# SCH_Grove_Lepton_camera_2022-09-28.net
KiCad netlist of a schematic drawn in EasyEDA
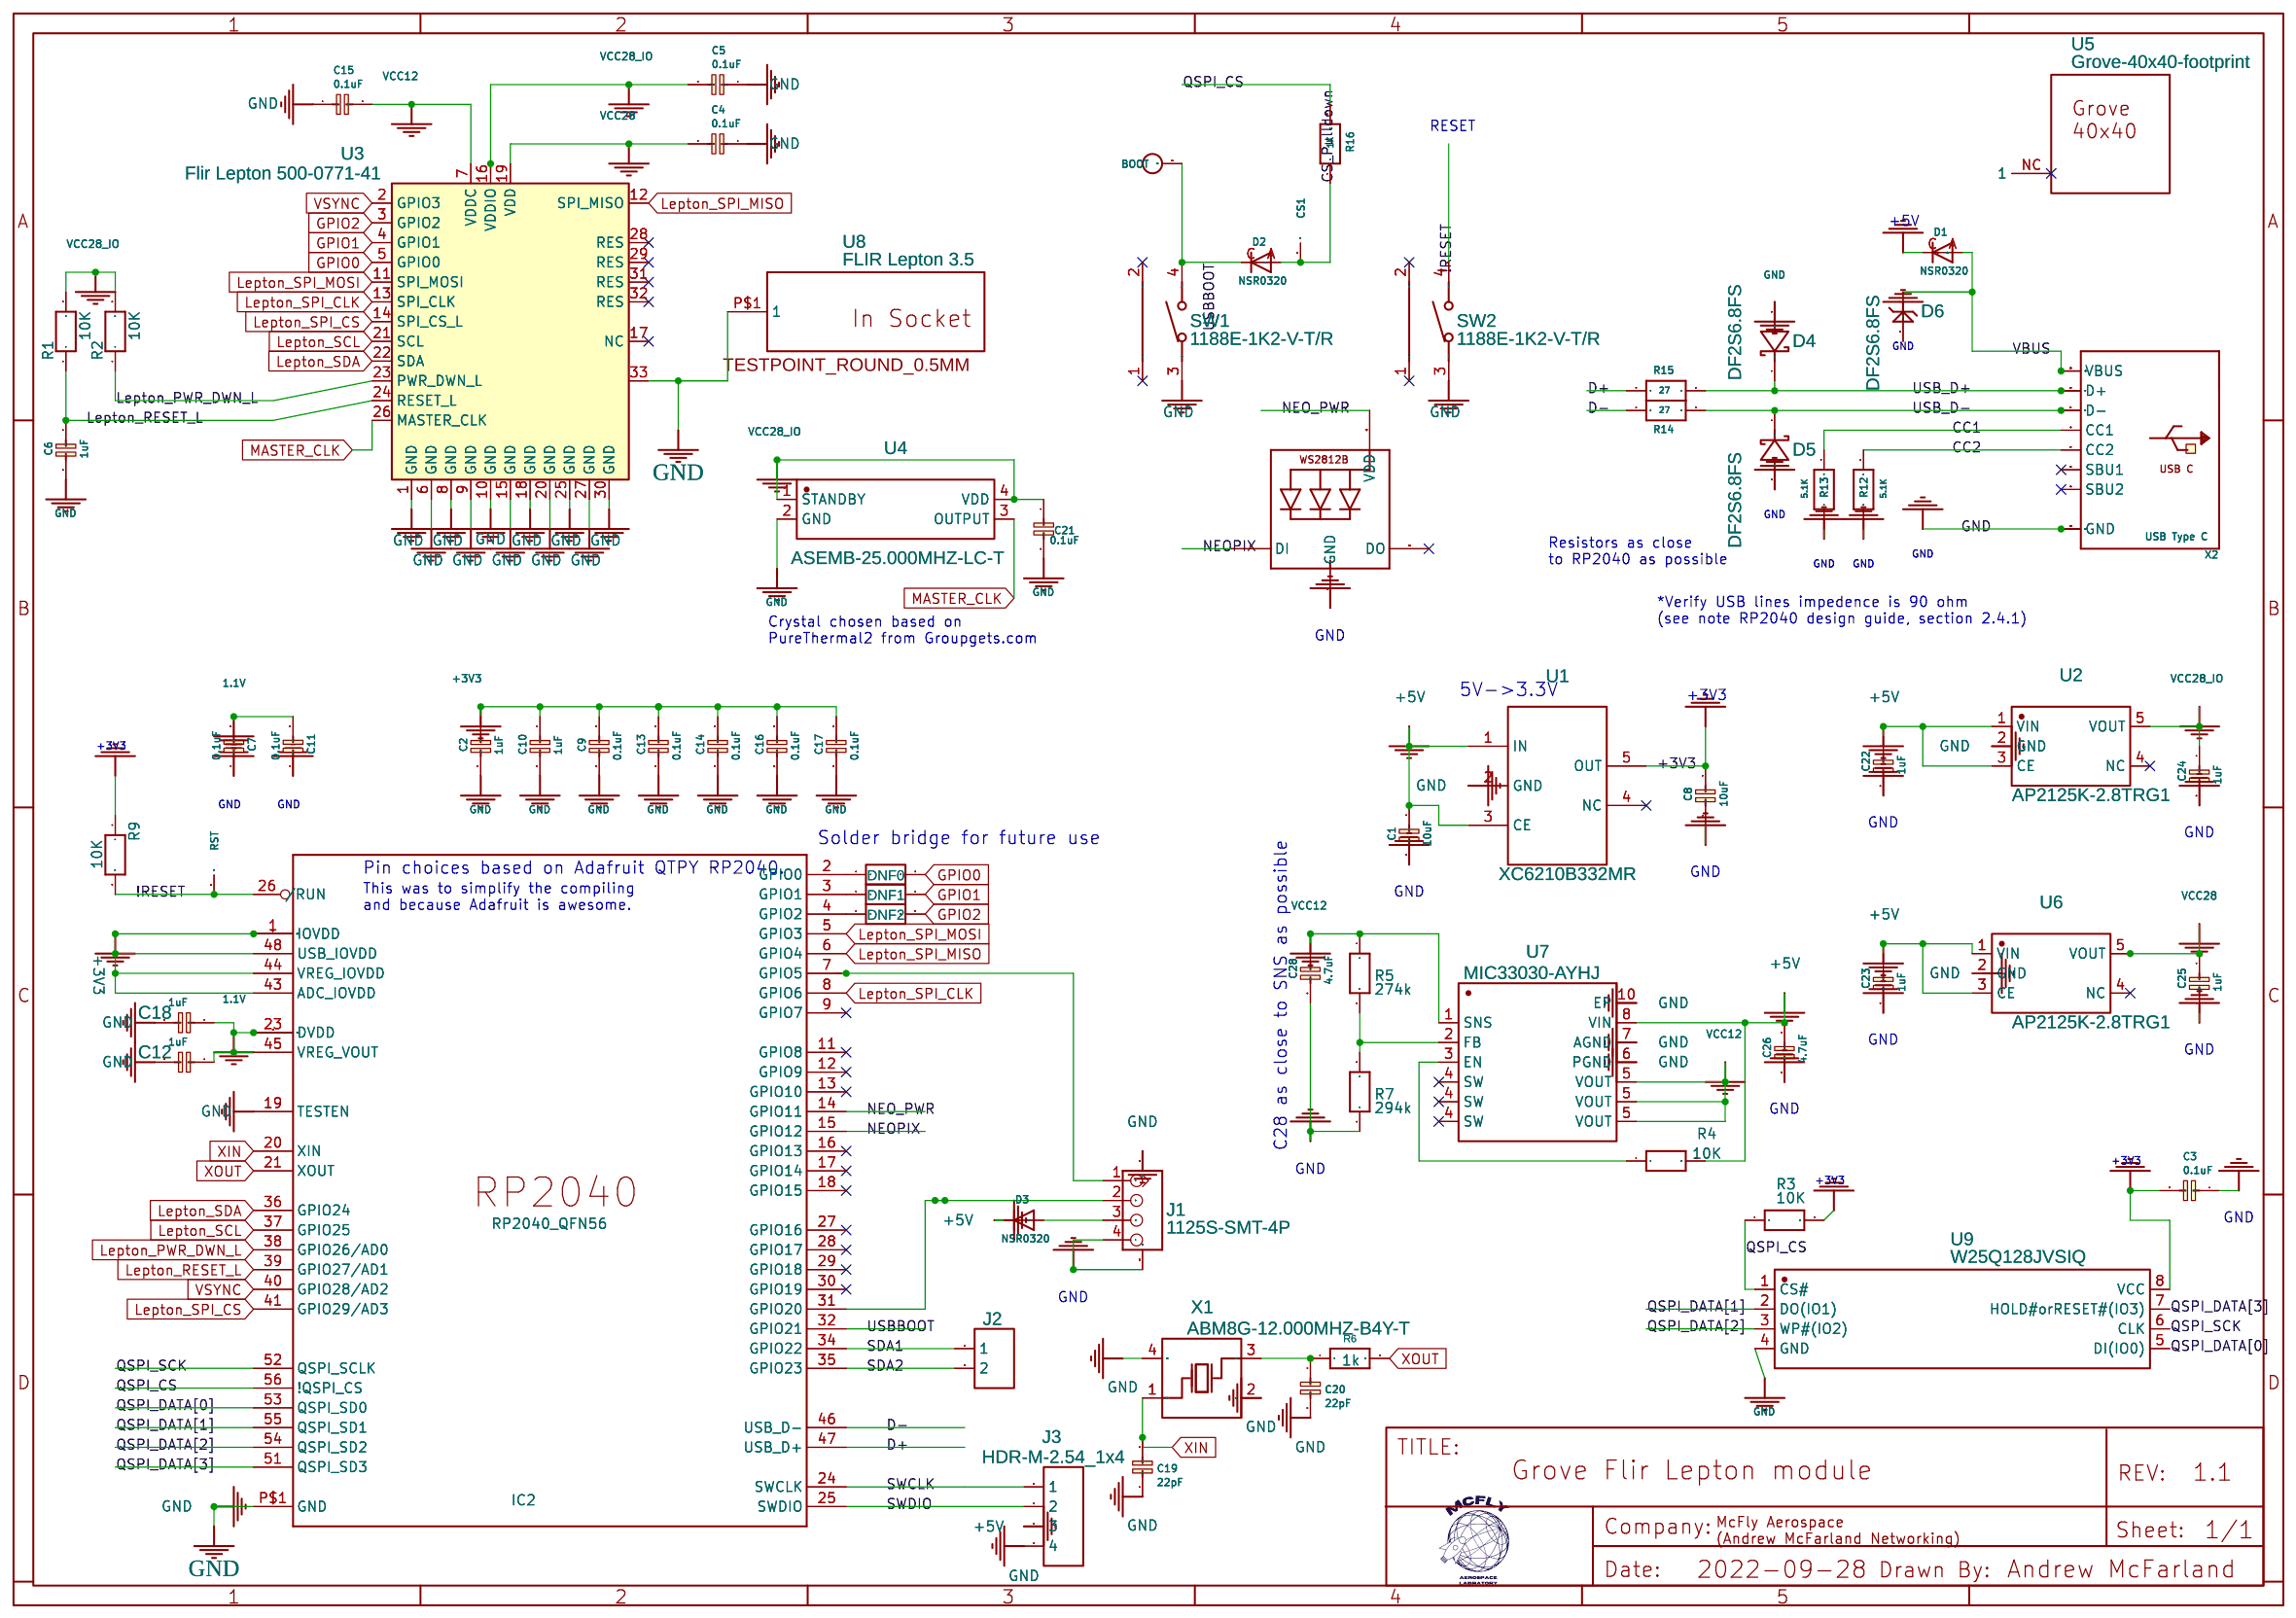
[diagram p0: schematic sheet]

(export (version "E")
  (design (tool "Eeschema 10.0.6"))
  (components
    (comp (ref "BOOT") (value "TESTPOINTROUND1.5MMNO") (libsource (lib "") (part "Unknown_595_-730")))
    (comp (ref "C1")
      (value "10uF")
      (fields
        (field (name "Manufacturer Part") "CC0805ZKY5V6BB106")
        (field (name "BOM_Supplier Part") "302010158")
      )
      (libsource (lib "") (part "Unknown_710_-385"))
    )
    (comp (ref "C2")
      (value "1uF")
      (fields
        (field (name "Manufacturer Part") "CC0603KRX7R8BB105")
        (field (name "BOM_Supplier Part") "302010139")
      )
      (libsource (lib "") (part "Unknown_240_-430"))
    )
    (comp (ref "C3")
      (value "0.1uF")
      (fields
        (field (name "Manufacturer Part") "CC0402KRX7R7BB104")
        (field (name "BOM_Supplier Part") "302010004")
      )
      (libsource (lib "") (part "Unknown_1100_-210"))
    )
    (comp (ref "C4") (value "0.1uF") (libsource (lib "") (part "Unknown_355_-740")))
    (comp (ref "C5") (value "0.1uF") (libsource (lib "") (part "Unknown_355_-770")))
    (comp (ref "C6") (value "1uF") (libsource (lib "") (part "Unknown_30_-580")))
    (comp (ref "C7") (value "0.1uF") (libsource (lib "") (part "Unknown_115_-440")))
    (comp (ref "C8") (value "10uF") (libsource (lib "") (part "Unknown_860_-405")))
    (comp (ref "C9") (value "0.1uF") (libsource (lib "") (part "Unknown_300_-430")))
    (comp (ref "C10") (value "1uF") (libsource (lib "") (part "Unknown_270_-430")))
    (comp (ref "C11") (value "0.1uF") (libsource (lib "") (part "Unknown_145_-440")))
    (comp (ref "C12") (value "1uF") (libsource (lib "") (part "Unknown_85_-275")))
    (comp (ref "C13") (value "0.1uF") (libsource (lib "") (part "Unknown_330_-430")))
    (comp (ref "C14") (value "0.1uF") (libsource (lib "") (part "Unknown_360_-430")))
    (comp (ref "C15") (value "0.1uF") (libsource (lib "") (part "Unknown_175_-760")))
    (comp (ref "C16") (value "0.1uF") (libsource (lib "") (part "Unknown_390_-430")))
    (comp (ref "C17") (value "0.1uF") (libsource (lib "") (part "Unknown_420_-430")))
    (comp (ref "C18") (value "1uF") (libsource (lib "") (part "Unknown_85_-295")))
    (comp (ref "C19") (value "22pF") (libsource (lib "") (part "Unknown_575_-75")))
    (comp (ref "C20")
      (value "22pF")
      (fields
        (field (name "Manufacturer Part") "CC0402JRNPO9BN220")
        (field (name "BOM_Supplier Part") "302010018")
      )
      (libsource (lib "") (part "Unknown_660_-105"))
    )
    (comp (ref "C21") (value "0.1uF") (libsource (lib "") (part "Unknown_525_-540")))
    (comp (ref "C22") (value "1uF") (libsource (lib "") (part "Unknown_950_-420")))
    (comp (ref "C23") (value "1uF") (libsource (lib "") (part "Unknown_950_-310")))
    (comp (ref "C24") (value "1uF") (libsource (lib "") (part "Unknown_1110_-415")))
    (comp (ref "C25") (value "1uF") (libsource (lib "") (part "Unknown_1110_-310")))
    (comp (ref "C26")
      (value "4.7uF")
      (fields
        (field (name "Manufacturer Part") "CC0805KKX5R8BB475")
        (field (name "BOM_Supplier Part") "302010146")
      )
      (libsource (lib "") (part "Unknown_900_-275"))
    )
    (comp (ref "C28")
      (value "4.7uF")
      (fields (field (name "BOM_Supplier Part") "302010146"))
      (libsource (lib "") (part "Unknown_660_-315"))
    )
    (comp (ref "CS1") (value "TESTPOINTROUND1.5MMNO") (libsource (lib "") (part "Unknown_655_-680")))
    (comp (ref "D1")
      (value "NSR0320")
      (fields
        (field (name "Manufacturer Part") "NSR0320MW2T1G")
        (field (name "BOM_Supplier Part") "NSR0320MW2T1GOSTR-ND")
      )
      (libsource (lib "") (part "Unknown_980_-685"))
    )
    (comp (ref "D2")
      (value "NSR0320")
      (fields
        (field (name "Manufacturer Part") "NSR0320MW2T1G")
        (field (name "BOM_Supplier Part") "NSR0320MW2T1GOSCT-ND")
      )
      (libsource (lib "") (part "Unknown_635_-680"))
    )
    (comp (ref "D3")
      (value "NSR0320")
      (fields
        (field (name "Manufacturer Part") "NSR0320MW2T1G")
        (field (name "BOM_Supplier Part") "NSR0320MW2T1GOSCT-ND")
      )
      (libsource (lib "") (part "Unknown_515_-195"))
    )
    (comp (ref "D4")
      (value "DF2S6.8FS")
      (fields
        (field (name "BOM_Manufacturer Part") "DF2S6.8FS,L3M")
        (field (name "BOM_Supplier Part") "304060009")
      )
      (libsource (lib "") (part "DF2S6.8FS,L3M"))
    )
    (comp (ref "D5")
      (value "DF2S6.8FS")
      (fields
        (field (name "BOM_Manufacturer Part") "DF2S6.8FS,L3M")
        (field (name "BOM_Supplier Part") "304060009")
      )
      (libsource (lib "") (part "DF2S6.8FS,L3M_1"))
    )
    (comp (ref "D6")
      (value "DF2S6.8FS")
      (fields (field (name "BOM_Supplier Part") "304060009"))
      (libsource (lib "") (part "D-ESD-2PDF2S6.8FS"))
    )
    (comp (ref "DNF0") (value "DNF") (libsource (lib "") (part "R_0603_EU")))
    (comp (ref "DNF1") (value "DNF") (libsource (lib "") (part "R_0603_EU")))
    (comp (ref "DNF2") (value "DNF") (libsource (lib "") (part "R_0603_EU")))
    (comp (ref "IC2")
      (value "RP2040_QFN56")
      (fields (field (name "Manufacturer Part") "RP2040") (field (name "BOM_Supplier Part") "310011401"))
      (libsource (lib "") (part "Unknown_275_-210"))
    )
    (comp (ref "J1")
      (value "1125S-SMT-4P")
      (fields (field (name "BOM_Supplier Part") "320110030"))
      (libsource (lib "") (part "1125S-SMT-4P"))
    )
    (comp (ref "J2") (value "HDR-F-2.54_1x2") (libsource (lib "") (part "HDR-F-2.54_1x2")))
    (comp (ref "J3") (value "HDR-M-2.54_1x4") (libsource (lib "") (part "HDR-M-2.54_1x4")))
    (comp (ref "LED1")
      (value "WS2812B_SK6805_1515")
      (fields (field (name "Manufacturer Part") "WS2812B-V5") (field (name "BOM_Supplier Part") "304091310"))
      (libsource (lib "") (part "Unknown_670_-545"))
    )
    (comp (ref "R1")
      (value "10K")
      (fields
        (field (name "Manufacturer Part") "RC0402JR-0710KL")
        (field (name "BOM_Supplier Part") "301010004")
      )
      (libsource (lib "") (part "Unknown_30_-645"))
    )
    (comp (ref "R2")
      (value "10K")
      (fields
        (field (name "Manufacturer Part") "RC0402JR-0710KL")
        (field (name "BOM_Supplier Part") "301010004")
      )
      (libsource (lib "") (part "Unknown_55_-645"))
    )
    (comp (ref "R3")
      (value "10K")
      (fields
        (field (name "Manufacturer Part") "RC0402JR-0710KL")
        (field (name "BOM_Supplier Part") "301010004")
      )
      (libsource (lib "") (part "Unknown_900_-195"))
    )
    (comp (ref "R4")
      (value "10K")
      (fields
        (field (name "Manufacturer Part") "RC0402JR-0710KL")
        (field (name "BOM_Supplier Part") "301010004")
      )
      (libsource (lib "") (part "Unknown_840_-225"))
    )
    (comp (ref "R5")
      (value "274k")
      (fields (field (name "BOM_Supplier Part") "RC0402FR-07274KL"))
      (libsource (lib "") (part "Unknown_685_-320"))
    )
    (comp (ref "R6")
      (value "1k")
      (fields
        (field (name "Manufacturer Part") "RC0402FR-071KL")
        (field (name "BOM_Supplier Part") "301010044")
      )
      (libsource (lib "") (part "Unknown_680_-125"))
    )
    (comp (ref "R7")
      (value "294k")
      (fields (field (name "BOM_Supplier Part") "RC0402FR-07294KL"))
      (libsource (lib "") (part "Unknown_685_-260"))
    )
    (comp (ref "R9")
      (value "10K")
      (fields
        (field (name "Manufacturer Part") "RC0402JR-0710KL")
        (field (name "BOM_Supplier Part") "301010004")
      )
      (libsource (lib "") (part "Unknown_55_-380"))
    )
    (comp (ref "R12")
      (value "5.1K")
      (fields
        (field (name "Manufacturer Part") "RC0402FR-075K1L")
        (field (name "BOM_Supplier Part") "301010495")
      )
      (libsource (lib "") (part "Unknown_940_-565"))
    )
    (comp (ref "R13")
      (value "5.1K")
      (fields
        (field (name "Manufacturer Part") "RC0402FR-075K1L")
        (field (name "BOM_Supplier Part") "301010495")
      )
      (libsource (lib "") (part "Unknown_920_-565"))
    )
    (comp (ref "R14")
      (value "27")
      (fields
        (field (name "Manufacturer Part") "RC0603FR-0727RL")
        (field (name "BOM_Supplier Part") "301011528")
      )
      (libsource (lib "") (part "Unknown_840_-605"))
    )
    (comp (ref "R15")
      (value "27")
      (fields
        (field (name "Manufacturer Part") "RC0603FR-0727RL")
        (field (name "BOM_Supplier Part") "301011528")
      )
      (libsource (lib "") (part "Unknown_840_-615"))
    )
    (comp (ref "R16")
      (value "1K")
      (fields
        (field (name "Manufacturer Part") "RC0402FR-071KL")
        (field (name "BOM_Supplier Part") "301010044")
      )
      (libsource (lib "") (part "Unknown_670_-740"))
    )
    (comp (ref "RST") (value "TESTPOINTROUND1.5MMNO") (libsource (lib "") (part "Unknown_105_-360")))
    (comp (ref "SW1")
      (value "1188E-1K2-V-T/R")
      (fields (field (name "BOM_Supplier Part") "311020023"))
      (libsource (lib "") (part "1188E-1K2-V-T/R"))
    )
    (comp (ref "SW2")
      (value "1188E-1K2-V-T/R")
      (fields (field (name "BOM_Supplier Part") "311020023"))
      (libsource (lib "") (part "1188E-1K2-V-T/R"))
    )
    (comp (ref "U1")
      (value "XC6210B332MR")
      (fields (field (name "BOM_Supplier Part") "893-1075-1-ND"))
      (libsource (lib "") (part "XC6210B332MR"))
    )
    (comp (ref "U2")
      (value "AP2125K-2.8TRG1")
      (fields (field (name "BOM_Supplier Part") "AP2125K-2.8TRG1DICT-ND"))
      (libsource (lib "") (part "AP2125K-2.8TRG1"))
    )
    (comp (ref "U3")
      (value "Flir Lepton 500-0771-41")
      (fields
        (field (name "BOM_Manufacturer Part") "1050281001")
        (field (name "BOM_Supplier Part") "WM6827CT-ND")
      )
      (libsource (lib "") (part "500-0643-00"))
    )
    (comp (ref "U4")
      (value "ASEMB-25.000MHZ-LC-T")
      (fields (field (name "BOM_Manufacturer Part") "535-11750-2-ND - 卷带（TR） 535-11750-1-ND"))
      (libsource (lib "") (part "ASEMB-25.000MHZ-LY-T"))
    )
    (comp (ref "U5") (value "Grove-40x40-footprint") (libsource (lib "") (part "Grove-40x40-footprint")))
    (comp (ref "U6")
      (value "AP2125K-2.8TRG1")
      (fields (field (name "BOM_Supplier Part") "AP2125K-2.8TRG1DICT-ND"))
      (libsource (lib "") (part "AP2125K-2.8TRG1"))
    )
    (comp (ref "U7")
      (value "MIC33030-AYHJ")
      (fields
        (field (name "BOM_Manufacturer Part") "MIC33030-AYHJ-TR")
        (field (name "BOM_Supplier Part") "998-MIC33030-AYHJTR")
      )
      (libsource (lib "") (part "MIC33030-AYHJ-TR"))
    )
    (comp (ref "U8")
      (value "FLIR Lepton 3.5")
      (fields
        (field (name "BOM_Manufacturer Part") "500-0771-01-ND")
        (field (name "BOM_Supplier Part") "500-0771-01")
      )
      (libsource (lib "") (part "lepton"))
    )
    (comp (ref "U9") (value "W25Q128JVSIQ") (libsource (lib "") (part "W25Q128JVSIQ")))
    (comp (ref "X1") (value "ABM8G-12.000MHZ-B4Y-T") (libsource (lib "") (part "ABM8G-12.000MHZ-B4Y-T")))
    (comp (ref "X2") (value "USB Type C") (libsource (lib "") (part "Unknown_1080_-585")))
  )
  (nets
    (net (code "1") (name "+3V3") (class "Default")
      (node (ref "C10") (pin "1") (pinfunction "1_1") (pintype "bidirectional"))
      (node (ref "C13") (pin "1") (pinfunction "1_1") (pintype "bidirectional"))
      (node (ref "C14") (pin "1") (pinfunction "1_1") (pintype "bidirectional"))
      (node (ref "C16") (pin "1") (pinfunction "1_1") (pintype "bidirectional"))
      (node (ref "C17") (pin "1") (pinfunction "1_1") (pintype "bidirectional"))
      (node (ref "C2") (pin "1") (pinfunction "1_1") (pintype "bidirectional"))
      (node (ref "C3") (pin "2") (pinfunction "2_2") (pintype "bidirectional"))
      (node (ref "C8") (pin "1") (pinfunction "1_1") (pintype "bidirectional"))
      (node (ref "C9") (pin "1") (pinfunction "1_1") (pintype "bidirectional"))
      (node (ref "IC2") (pin "1") (pinfunction "IOVDD_1") (pintype "bidirectional"))
      (node (ref "IC2") (pin "10") (pinfunction "IOVDD_10") (pintype "bidirectional"))
      (node (ref "IC2") (pin "22") (pinfunction "IOVDD_22") (pintype "bidirectional"))
      (node (ref "IC2") (pin "33") (pinfunction "IOVDD_33") (pintype "bidirectional"))
      (node (ref "IC2") (pin "42") (pinfunction "IOVDD_42") (pintype "bidirectional"))
      (node (ref "IC2") (pin "43") (pinfunction "ADC_IOVDD_43") (pintype "bidirectional"))
      (node (ref "IC2") (pin "44") (pinfunction "VREG_IOVDD_44") (pintype "bidirectional"))
      (node (ref "IC2") (pin "48") (pinfunction "USB_IOVDD_48") (pintype "bidirectional"))
      (node (ref "IC2") (pin "49") (pinfunction "IOVDD_49") (pintype "bidirectional"))
      (node (ref "R3") (pin "2") (pinfunction "2_2") (pintype "bidirectional"))
      (node (ref "R9") (pin "1") (pinfunction "1_1") (pintype "bidirectional"))
      (node (ref "U1") (pin "5") (pinfunction "OUT_5") (pintype "unspecified"))
      (node (ref "U9") (pin "8") (pinfunction "VCC_8") (pintype "unspecified"))
    )
    (net (code "2") (name "+5V") (class "Default")
      (node (ref "C1") (pin "1") (pinfunction "1_1") (pintype "bidirectional"))
      (node (ref "C22") (pin "1") (pinfunction "1_1") (pintype "bidirectional"))
      (node (ref "C23") (pin "1") (pinfunction "1_1") (pintype "bidirectional"))
      (node (ref "C26") (pin "1") (pinfunction "1_1") (pintype "bidirectional"))
      (node (ref "D1") (pin "C") (pinfunction "Cathode_C") (pintype "bidirectional"))
      (node (ref "D3") (pin "C") (pinfunction "C_C") (pintype "bidirectional"))
      (node (ref "J3") (pin "3") (pinfunction "3_3") (pintype "unspecified"))
      (node (ref "R4") (pin "2") (pinfunction "2_2") (pintype "bidirectional"))
      (node (ref "U1") (pin "1") (pinfunction "IN_1") (pintype "unspecified"))
      (node (ref "U1") (pin "3") (pinfunction "CE_3") (pintype "unspecified"))
      (node (ref "U2") (pin "1") (pinfunction "VIN_1") (pintype "unspecified"))
      (node (ref "U2") (pin "3") (pinfunction "CE_3") (pintype "unspecified"))
      (node (ref "U6") (pin "1") (pinfunction "VIN_1") (pintype "unspecified"))
      (node (ref "U6") (pin "3") (pinfunction "CE_3") (pintype "unspecified"))
      (node (ref "U7") (pin "8") (pinfunction "VIN_8") (pintype "unspecified"))
    )
    (net (code "3") (name "/!RESET") (class "Default")
      (node (ref "IC2") (pin "26") (pinfunction "/RUN_26") (pintype "bidirectional"))
      (node (ref "R9") (pin "2") (pinfunction "2_2") (pintype "bidirectional"))
      (node (ref "RST") (pin "P$1") (pinfunction "P$1_P$1") (pintype "bidirectional"))
      (node (ref "SW2") (pin "4") (pinfunction "4_4") (pintype "unspecified"))
    )
    (net (code "4") (name "/CC1") (class "Default")
      (node (ref "R13") (pin "2") (pinfunction "2_2") (pintype "bidirectional"))
      (node (ref "X2") (pin "A5") (pinfunction "CC1_A5") (pintype "bidirectional"))
    )
    (net (code "5") (name "/CC2") (class "Default")
      (node (ref "R12") (pin "2") (pinfunction "2_2") (pintype "bidirectional"))
      (node (ref "X2") (pin "B5") (pinfunction "CC2_B5") (pintype "bidirectional"))
    )
    (net (code "6") (name "/CS_Pulldown") (class "Default")
      (node (ref "CS1") (pin "P$1") (pinfunction "P$1_P$1") (pintype "bidirectional"))
      (node (ref "D2") (pin "A") (pinfunction "A_A") (pintype "bidirectional"))
      (node (ref "R16") (pin "2") (pinfunction "2_2") (pintype "bidirectional"))
    )
    (net (code "7") (name "/D+") (class "Default")
      (node (ref "IC2") (pin "47") (pinfunction "USB_D+_47") (pintype "bidirectional"))
      (node (ref "R15") (pin "2") (pinfunction "2_2") (pintype "bidirectional"))
    )
    (net (code "8") (name "/D-") (class "Default")
      (node (ref "IC2") (pin "46") (pinfunction "USB_D-_46") (pintype "bidirectional"))
      (node (ref "R14") (pin "2") (pinfunction "2_2") (pintype "bidirectional"))
    )
    (net (code "9") (name "/NEOPIX") (class "Default")
      (node (ref "IC2") (pin "15") (pinfunction "GPIO12_15") (pintype "bidirectional"))
      (node (ref "LED1") (pin "4-DIN") (pinfunction "DI_4-DIN") (pintype "bidirectional"))
    )
    (net (code "10") (name "/NEO_PWR") (class "Default")
      (node (ref "IC2") (pin "14") (pinfunction "GPIO11_14") (pintype "bidirectional"))
      (node (ref "LED1") (pin "1-VDD") (pinfunction "VDD_1-VDD") (pintype "bidirectional"))
    )
    (net (code "11") (name "/QSPI_CS") (class "Default")
      (node (ref "IC2") (pin "56") (pinfunction "!QSPI_CS_56") (pintype "bidirectional"))
      (node (ref "R16") (pin "1") (pinfunction "1_1") (pintype "bidirectional"))
      (node (ref "R3") (pin "1") (pinfunction "1_1") (pintype "bidirectional"))
      (node (ref "U9") (pin "1") (pinfunction "CS#_1") (pintype "unspecified"))
    )
    (net (code "12") (name "/QSPI_DATA[0]") (class "Default")
      (node (ref "IC2") (pin "53") (pinfunction "QSPI_SD0_53") (pintype "bidirectional"))
      (node (ref "U9") (pin "5") (pinfunction "DI(IO0)_5") (pintype "unspecified"))
    )
    (net (code "13") (name "/QSPI_DATA[1]") (class "Default")
      (node (ref "IC2") (pin "55") (pinfunction "QSPI_SD1_55") (pintype "bidirectional"))
      (node (ref "U9") (pin "2") (pinfunction "DO(IO1)_2") (pintype "unspecified"))
    )
    (net (code "14") (name "/QSPI_DATA[2]") (class "Default")
      (node (ref "IC2") (pin "54") (pinfunction "QSPI_SD2_54") (pintype "bidirectional"))
      (node (ref "U9") (pin "3") (pinfunction "WP#(IO2)_3") (pintype "unspecified"))
    )
    (net (code "15") (name "/QSPI_DATA[3]") (class "Default")
      (node (ref "IC2") (pin "51") (pinfunction "QSPI_SD3_51") (pintype "bidirectional"))
      (node (ref "U9") (pin "7") (pinfunction "HOLD#orRESET#(IO3)_7") (pintype "unspecified"))
    )
    (net (code "16") (name "/QSPI_SCK") (class "Default")
      (node (ref "IC2") (pin "52") (pinfunction "QSPI_SCLK_52") (pintype "bidirectional"))
      (node (ref "U9") (pin "6") (pinfunction "CLK_6") (pintype "unspecified"))
    )
    (net (code "17") (name "/SDA1") (class "Default")
      (node (ref "IC2") (pin "34") (pinfunction "GPIO22_34") (pintype "bidirectional"))
      (node (ref "J2") (pin "1") (pinfunction "1_1") (pintype "input"))
    )
    (net (code "18") (name "/SDA2") (class "Default")
      (node (ref "IC2") (pin "35") (pinfunction "GPIO23_35") (pintype "bidirectional"))
      (node (ref "J2") (pin "2") (pinfunction "2_2") (pintype "input"))
    )
    (net (code "19") (name "/SWCLK") (class "Default")
      (node (ref "IC2") (pin "24") (pinfunction "SWCLK_24") (pintype "bidirectional"))
      (node (ref "J3") (pin "1") (pinfunction "1_1") (pintype "unspecified"))
    )
    (net (code "20") (name "/SWDIO") (class "Default")
      (node (ref "IC2") (pin "25") (pinfunction "SWDIO_25") (pintype "bidirectional"))
      (node (ref "J3") (pin "2") (pinfunction "2_2") (pintype "unspecified"))
    )
    (net (code "21") (name "/USBBOOT") (class "Default")
      (node (ref "BOOT") (pin "P$1") (pinfunction "P$1_P$1") (pintype "bidirectional"))
      (node (ref "D2") (pin "C") (pinfunction "C_C") (pintype "bidirectional"))
      (node (ref "IC2") (pin "32") (pinfunction "GPIO21_32") (pintype "bidirectional"))
      (node (ref "SW1") (pin "4") (pinfunction "4_4") (pintype "unspecified"))
    )
    (net (code "22") (name "/USB_D+") (class "Default")
      (node (ref "D4") (pin "1") (pinfunction "1_1") (pintype "unspecified"))
      (node (ref "R15") (pin "1") (pinfunction "1_1") (pintype "bidirectional"))
      (node (ref "X2") (pin "A6") (pinfunction "D+_A6") (pintype "bidirectional"))
      (node (ref "X2") (pin "B6") (pinfunction "D+_B6") (pintype "bidirectional"))
    )
    (net (code "23") (name "/USB_D-") (class "Default")
      (node (ref "D5") (pin "1") (pinfunction "1_1") (pintype "unspecified"))
      (node (ref "R14") (pin "1") (pinfunction "1_1") (pintype "bidirectional"))
      (node (ref "X2") (pin "A7") (pinfunction "D-_A7") (pintype "bidirectional"))
      (node (ref "X2") (pin "B7") (pinfunction "D-_B7") (pintype "bidirectional"))
    )
    (net (code "24") (name "/VBUS") (class "Default")
      (node (ref "D1") (pin "A") (pinfunction "Anode_A") (pintype "bidirectional"))
      (node (ref "D6") (pin "1") (pinfunction "2_1") (pintype "unspecified"))
      (node (ref "X2") (pin "A4B9") (pinfunction "VBUS_A4B9") (pintype "bidirectional"))
      (node (ref "X2") (pin "B4A9") (pinfunction "VBUS_B4A9") (pintype "bidirectional"))
    )
    (net (code "25") (name "1.1V") (class "Default")
      (node (ref "C11") (pin "2") (pinfunction "2_2") (pintype "bidirectional"))
      (node (ref "C12") (pin "1") (pinfunction "1_1") (pintype "bidirectional"))
      (node (ref "C18") (pin "1") (pinfunction "1_1") (pintype "bidirectional"))
      (node (ref "C7") (pin "2") (pinfunction "2_2") (pintype "bidirectional"))
      (node (ref "IC2") (pin "23") (pinfunction "DVDD_23") (pintype "bidirectional"))
      (node (ref "IC2") (pin "45") (pinfunction "VREG_VOUT_45") (pintype "bidirectional"))
      (node (ref "IC2") (pin "50") (pinfunction "DVDD_50") (pintype "bidirectional"))
    )
    (net (code "26") (name "GND") (class "Default")
      (node (ref "C1") (pin "2") (pinfunction "2_2") (pintype "bidirectional"))
      (node (ref "C10") (pin "2") (pinfunction "2_2") (pintype "bidirectional"))
      (node (ref "C11") (pin "1") (pinfunction "1_1") (pintype "bidirectional"))
      (node (ref "C12") (pin "2") (pinfunction "2_2") (pintype "bidirectional"))
      (node (ref "C13") (pin "2") (pinfunction "2_2") (pintype "bidirectional"))
      (node (ref "C14") (pin "2") (pinfunction "2_2") (pintype "bidirectional"))
      (node (ref "C15") (pin "1") (pinfunction "1_1") (pintype "bidirectional"))
      (node (ref "C16") (pin "2") (pinfunction "2_2") (pintype "bidirectional"))
      (node (ref "C17") (pin "2") (pinfunction "2_2") (pintype "bidirectional"))
      (node (ref "C18") (pin "2") (pinfunction "2_2") (pintype "bidirectional"))
      (node (ref "C19") (pin "1") (pinfunction "1_1") (pintype "bidirectional"))
      (node (ref "C2") (pin "2") (pinfunction "2_2") (pintype "bidirectional"))
      (node (ref "C20") (pin "2") (pinfunction "2_2") (pintype "bidirectional"))
      (node (ref "C21") (pin "2") (pinfunction "2_2") (pintype "bidirectional"))
      (node (ref "C22") (pin "2") (pinfunction "2_2") (pintype "bidirectional"))
      (node (ref "C23") (pin "2") (pinfunction "2_2") (pintype "bidirectional"))
      (node (ref "C24") (pin "2") (pinfunction "2_2") (pintype "bidirectional"))
      (node (ref "C25") (pin "2") (pinfunction "2_2") (pintype "bidirectional"))
      (node (ref "C26") (pin "2") (pinfunction "2_2") (pintype "bidirectional"))
      (node (ref "C28") (pin "2") (pinfunction "2_2") (pintype "bidirectional"))
      (node (ref "C3") (pin "1") (pinfunction "1_1") (pintype "bidirectional"))
      (node (ref "C4") (pin "1") (pinfunction "1_1") (pintype "bidirectional"))
      (node (ref "C5") (pin "1") (pinfunction "1_1") (pintype "bidirectional"))
      (node (ref "C6") (pin "2") (pinfunction "2_2") (pintype "bidirectional"))
      (node (ref "C7") (pin "1") (pinfunction "1_1") (pintype "bidirectional"))
      (node (ref "C8") (pin "2") (pinfunction "2_2") (pintype "bidirectional"))
      (node (ref "C9") (pin "2") (pinfunction "2_2") (pintype "bidirectional"))
      (node (ref "D4") (pin "2") (pinfunction "2_2") (pintype "unspecified"))
      (node (ref "D5") (pin "2") (pinfunction "2_2") (pintype "unspecified"))
      (node (ref "D6") (pin "2") (pinfunction "1_2") (pintype "unspecified"))
      (node (ref "IC2") (pin "19") (pinfunction "TESTEN_19") (pintype "bidirectional"))
      (node (ref "IC2") (pin "P$1") (pinfunction "GND_P$1") (pintype "bidirectional"))
      (node (ref "J1") (pin "4") (pinfunction "4_4") (pintype "unspecified"))
      (node (ref "J1") (pin "SS1") (pinfunction "SS1_SS1") (pintype "unspecified"))
      (node (ref "J1") (pin "SS2") (pinfunction "SS2_SS2") (pintype "unspecified"))
      (node (ref "J3") (pin "4") (pinfunction "4_4") (pintype "unspecified"))
      (node (ref "LED1") (pin "3-GND") (pinfunction "GND_3-GND") (pintype "bidirectional"))
      (node (ref "R12") (pin "1") (pinfunction "1_1") (pintype "bidirectional"))
      (node (ref "R13") (pin "1") (pinfunction "1_1") (pintype "bidirectional"))
      (node (ref "R7") (pin "2") (pinfunction "2_2") (pintype "bidirectional"))
      (node (ref "SW1") (pin "3") (pinfunction "3_3") (pintype "unspecified"))
      (node (ref "SW2") (pin "3") (pinfunction "3_3") (pintype "unspecified"))
      (node (ref "U1") (pin "2") (pinfunction "GND_2") (pintype "unspecified"))
      (node (ref "U2") (pin "2") (pinfunction "GND_2") (pintype "unspecified"))
      (node (ref "U3") (pin "1") (pinfunction "GND_1") (pintype "bidirectional"))
      (node (ref "U3") (pin "10") (pinfunction "GND_10") (pintype "bidirectional"))
      (node (ref "U3") (pin "15") (pinfunction "GND_15") (pintype "bidirectional"))
      (node (ref "U3") (pin "18") (pinfunction "GND_18") (pintype "bidirectional"))
      (node (ref "U3") (pin "20") (pinfunction "GND_20") (pintype "bidirectional"))
      (node (ref "U3") (pin "25") (pinfunction "GND_25") (pintype "bidirectional"))
      (node (ref "U3") (pin "27") (pinfunction "GND_27") (pintype "bidirectional"))
      (node (ref "U3") (pin "30") (pinfunction "GND_30") (pintype "bidirectional"))
      (node (ref "U3") (pin "33") (pintype "unspecified"))
      (node (ref "U3") (pin "6") (pinfunction "GND_6") (pintype "bidirectional"))
      (node (ref "U3") (pin "8") (pinfunction "GND_8") (pintype "bidirectional"))
      (node (ref "U3") (pin "9") (pinfunction "GND_9") (pintype "bidirectional"))
      (node (ref "U4") (pin "2") (pinfunction "GND_2") (pintype "unspecified"))
      (node (ref "U6") (pin "2") (pinfunction "GND_2") (pintype "unspecified"))
      (node (ref "U7") (pin "10") (pinfunction "EP_10") (pintype "unspecified"))
      (node (ref "U7") (pin "6") (pinfunction "PGND_6") (pintype "unspecified"))
      (node (ref "U7") (pin "7") (pinfunction "AGND_7") (pintype "unspecified"))
      (node (ref "U8") (pin "P$1") (pinfunction "1_P$1") (pintype "unspecified"))
      (node (ref "U9") (pin "4") (pinfunction "GND_4") (pintype "unspecified"))
      (node (ref "X1") (pin "2") (pinfunction "GND_2") (pintype "unspecified"))
      (node (ref "X1") (pin "4") (pinfunction "GND_4") (pintype "unspecified"))
      (node (ref "X2") (pin "A1B12") (pinfunction "GND_A1B12") (pintype "bidirectional"))
      (node (ref "X2") (pin "B1A12") (pinfunction "GND_B1A12") (pintype "bidirectional"))
    )
    (net (code "27") (name "GPIO0") (class "Default")
      (node (ref "DNF0") (pin "2") (pinfunction "2_2") (pintype "unspecified"))
      (node (ref "U3") (pin "5") (pinfunction "GPIO0_5") (pintype "bidirectional"))
    )
    (net (code "28") (name "GPIO1") (class "Default")
      (node (ref "DNF1") (pin "2") (pinfunction "2_2") (pintype "unspecified"))
      (node (ref "U3") (pin "4") (pinfunction "GPIO1_4") (pintype "bidirectional"))
    )
    (net (code "29") (name "GPIO2") (class "Default")
      (node (ref "DNF2") (pin "2") (pinfunction "2_2") (pintype "unspecified"))
      (node (ref "U3") (pin "3") (pinfunction "GPIO2_3") (pintype "bidirectional"))
    )
    (net (code "30") (name "Lepton_PWR_DWN_L") (class "Default")
      (node (ref "IC2") (pin "38") (pinfunction "GPIO26/AD0_38") (pintype "bidirectional"))
      (node (ref "R2") (pin "1") (pinfunction "1_1") (pintype "bidirectional"))
      (node (ref "U3") (pin "23") (pinfunction "PWR_DWN_L_23") (pintype "input"))
    )
    (net (code "31") (name "Lepton_RESET_L") (class "Default")
      (node (ref "C6") (pin "1") (pinfunction "1_1") (pintype "bidirectional"))
      (node (ref "IC2") (pin "39") (pinfunction "GPIO27/AD1_39") (pintype "bidirectional"))
      (node (ref "R1") (pin "1") (pinfunction "1_1") (pintype "bidirectional"))
      (node (ref "U3") (pin "24") (pinfunction "RESET_L_24") (pintype "input"))
    )
    (net (code "32") (name "Lepton_SCL") (class "Default")
      (node (ref "IC2") (pin "37") (pinfunction "GPIO25_37") (pintype "bidirectional"))
      (node (ref "U3") (pin "21") (pinfunction "SCL_21") (pintype "input"))
    )
    (net (code "33") (name "Lepton_SDA") (class "Default")
      (node (ref "IC2") (pin "36") (pinfunction "GPIO24_36") (pintype "bidirectional"))
      (node (ref "U3") (pin "22") (pinfunction "SDA_22") (pintype "bidirectional"))
    )
    (net (code "34") (name "Lepton_SPI_CLK") (class "Default")
      (node (ref "IC2") (pin "8") (pinfunction "GPIO6_8") (pintype "bidirectional"))
      (node (ref "U3") (pin "13") (pinfunction "SPI_CLK_13") (pintype "input"))
    )
    (net (code "35") (name "Lepton_SPI_CS") (class "Default")
      (node (ref "IC2") (pin "41") (pinfunction "GPIO29/AD3_41") (pintype "bidirectional"))
      (node (ref "U3") (pin "14") (pinfunction "SPI_CS_L_14") (pintype "input"))
    )
    (net (code "36") (name "Lepton_SPI_MISO") (class "Default")
      (node (ref "IC2") (pin "6") (pinfunction "GPIO4_6") (pintype "bidirectional"))
      (node (ref "U3") (pin "12") (pinfunction "SPI_MISO_12") (pintype "output"))
    )
    (net (code "37") (name "Lepton_SPI_MOSI") (class "Default")
      (node (ref "IC2") (pin "5") (pinfunction "GPIO3_5") (pintype "bidirectional"))
      (node (ref "U3") (pin "11") (pinfunction "SPI_MOSI_11") (pintype "input"))
    )
    (net (code "38") (name "MASTER_CLK") (class "Default")
      (node (ref "U3") (pin "26") (pinfunction "MASTER_CLK_26") (pintype "input"))
      (node (ref "U4") (pin "3") (pinfunction "OUTPUT_3") (pintype "unspecified"))
    )
    (net (code "39") (name "Net-(D3-PadA)") (class "Default")
      (node (ref "D3") (pin "A") (pinfunction "A_A") (pintype "bidirectional"))
      (node (ref "J1") (pin "3") (pinfunction "3_3") (pintype "unspecified"))
    )
    (net (code "40") (name "Net-(IC2-GPIO0)") (class "Default")
      (node (ref "DNF0") (pin "1") (pinfunction "1_1") (pintype "unspecified"))
      (node (ref "IC2") (pin "2") (pinfunction "GPIO0_2") (pintype "bidirectional"))
    )
    (net (code "41") (name "Net-(IC2-GPIO1)") (class "Default")
      (node (ref "DNF1") (pin "1") (pinfunction "1_1") (pintype "unspecified"))
      (node (ref "IC2") (pin "3") (pinfunction "GPIO1_3") (pintype "bidirectional"))
    )
    (net (code "42") (name "Net-(IC2-GPIO2)") (class "Default")
      (node (ref "DNF2") (pin "1") (pinfunction "1_1") (pintype "unspecified"))
      (node (ref "IC2") (pin "4") (pinfunction "GPIO2_4") (pintype "bidirectional"))
    )
    (net (code "43") (name "Net-(IC2-GPIO5)") (class "Default")
      (node (ref "IC2") (pin "7") (pinfunction "GPIO5_7") (pintype "bidirectional"))
      (node (ref "J1") (pin "1") (pinfunction "1_1") (pintype "unspecified"))
    )
    (net (code "44") (name "Net-(IC2-GPIO20)") (class "Default")
      (node (ref "IC2") (pin "31") (pinfunction "GPIO20_31") (pintype "bidirectional"))
      (node (ref "J1") (pin "2") (pinfunction "2_2") (pintype "unspecified"))
    )
    (net (code "45") (name "Net-(U7-EN)") (class "Default")
      (node (ref "R4") (pin "1") (pinfunction "1_1") (pintype "bidirectional"))
      (node (ref "U7") (pin "3") (pinfunction "EN_3") (pintype "unspecified"))
    )
    (net (code "46") (name "Net-(U7-FB)") (class "Default")
      (node (ref "R5") (pin "2") (pinfunction "2_2") (pintype "bidirectional"))
      (node (ref "R7") (pin "1") (pinfunction "1_1") (pintype "bidirectional"))
      (node (ref "U7") (pin "2") (pinfunction "FB_2") (pintype "unspecified"))
    )
    (net (code "47") (name "Net-(X1-OSC2)") (class "Default")
      (node (ref "C20") (pin "1") (pinfunction "1_1") (pintype "bidirectional"))
      (node (ref "R6") (pin "1") (pinfunction "1_1") (pintype "bidirectional"))
      (node (ref "X1") (pin "3") (pinfunction "OSC2_3") (pintype "unspecified"))
    )
    (net (code "48") (name "VCC12") (class "Default")
      (node (ref "C15") (pin "2") (pinfunction "2_2") (pintype "bidirectional"))
      (node (ref "C28") (pin "1") (pinfunction "1_1") (pintype "bidirectional"))
      (node (ref "R5") (pin "1") (pinfunction "1_1") (pintype "bidirectional"))
      (node (ref "U3") (pin "7") (pinfunction "VDDC_7") (pintype "bidirectional"))
      (node (ref "U7") (pin "1") (pinfunction "SNS_1") (pintype "unspecified"))
      (node (ref "U7") (pin "5") (pinfunction "VOUT_5") (pintype "unspecified"))
    )
    (net (code "49") (name "VCC28") (class "Default")
      (node (ref "C25") (pin "1") (pinfunction "1_1") (pintype "bidirectional"))
      (node (ref "C4") (pin "2") (pinfunction "2_2") (pintype "bidirectional"))
      (node (ref "U3") (pin "19") (pinfunction "VDD_19") (pintype "bidirectional"))
      (node (ref "U6") (pin "5") (pinfunction "VOUT_5") (pintype "unspecified"))
    )
    (net (code "50") (name "VCC28_IO") (class "Default")
      (node (ref "C21") (pin "1") (pinfunction "1_1") (pintype "bidirectional"))
      (node (ref "C24") (pin "1") (pinfunction "1_1") (pintype "bidirectional"))
      (node (ref "C5") (pin "2") (pinfunction "2_2") (pintype "bidirectional"))
      (node (ref "R1") (pin "2") (pinfunction "2_2") (pintype "bidirectional"))
      (node (ref "R2") (pin "2") (pinfunction "2_2") (pintype "bidirectional"))
      (node (ref "U2") (pin "5") (pinfunction "VOUT_5") (pintype "unspecified"))
      (node (ref "U3") (pin "16") (pinfunction "VDDIO_16") (pintype "bidirectional"))
      (node (ref "U4") (pin "1") (pinfunction "STANDBY_1") (pintype "unspecified"))
      (node (ref "U4") (pin "4") (pinfunction "VDD_4") (pintype "unspecified"))
    )
    (net (code "51") (name "VSYNC") (class "Default")
      (node (ref "IC2") (pin "40") (pinfunction "GPIO28/AD2_40") (pintype "bidirectional"))
      (node (ref "U3") (pin "2") (pinfunction "GPIO3_2") (pintype "bidirectional"))
    )
    (net (code "52") (name "XIN") (class "Default")
      (node (ref "C19") (pin "2") (pinfunction "2_2") (pintype "bidirectional"))
      (node (ref "IC2") (pin "20") (pinfunction "XIN_20") (pintype "bidirectional"))
      (node (ref "X1") (pin "1") (pinfunction "OSC1_1") (pintype "unspecified"))
    )
    (net (code "53") (name "XOUT") (class "Default")
      (node (ref "IC2") (pin "21") (pinfunction "XOUT_21") (pintype "bidirectional"))
      (node (ref "R6") (pin "2") (pinfunction "2_2") (pintype "bidirectional"))
    )
    (net (code "54") (name "unconnected-(IC2-GPIO7-Pad9)") (class "Default")
      (node (ref "IC2") (pin "9") (pinfunction "GPIO7_9") (pintype "bidirectional+no_connect"))
    )
    (net (code "55") (name "unconnected-(IC2-GPIO8-Pad11)") (class "Default")
      (node (ref "IC2") (pin "11") (pinfunction "GPIO8_11") (pintype "bidirectional+no_connect"))
    )
    (net (code "56") (name "unconnected-(IC2-GPIO9-Pad12)") (class "Default")
      (node (ref "IC2") (pin "12") (pinfunction "GPIO9_12") (pintype "bidirectional+no_connect"))
    )
    (net (code "57") (name "unconnected-(IC2-GPIO10-Pad13)") (class "Default")
      (node (ref "IC2") (pin "13") (pinfunction "GPIO10_13") (pintype "bidirectional+no_connect"))
    )
    (net (code "58") (name "unconnected-(IC2-GPIO13-Pad16)") (class "Default")
      (node (ref "IC2") (pin "16") (pinfunction "GPIO13_16") (pintype "bidirectional+no_connect"))
    )
    (net (code "59") (name "unconnected-(IC2-GPIO14-Pad17)") (class "Default")
      (node (ref "IC2") (pin "17") (pinfunction "GPIO14_17") (pintype "bidirectional+no_connect"))
    )
    (net (code "60") (name "unconnected-(IC2-GPIO15-Pad18)") (class "Default")
      (node (ref "IC2") (pin "18") (pinfunction "GPIO15_18") (pintype "bidirectional+no_connect"))
    )
    (net (code "61") (name "unconnected-(IC2-GPIO16-Pad27)") (class "Default")
      (node (ref "IC2") (pin "27") (pinfunction "GPIO16_27") (pintype "bidirectional+no_connect"))
    )
    (net (code "62") (name "unconnected-(IC2-GPIO17-Pad28)") (class "Default")
      (node (ref "IC2") (pin "28") (pinfunction "GPIO17_28") (pintype "bidirectional+no_connect"))
    )
    (net (code "63") (name "unconnected-(IC2-GPIO18-Pad29)") (class "Default")
      (node (ref "IC2") (pin "29") (pinfunction "GPIO18_29") (pintype "bidirectional+no_connect"))
    )
    (net (code "64") (name "unconnected-(IC2-GPIO19-Pad30)") (class "Default")
      (node (ref "IC2") (pin "30") (pinfunction "GPIO19_30") (pintype "bidirectional+no_connect"))
    )
    (net (code "65") (name "unconnected-(LED1-DO-Pad2-DOUT)") (class "Default")
      (node (ref "LED1") (pin "2-DOUT") (pinfunction "DO_2-DOUT") (pintype "bidirectional+no_connect"))
    )
    (net (code "66") (name "unconnected-(SW1-Pad1)") (class "Default")
      (node (ref "SW1") (pin "1") (pinfunction "1_1") (pintype "unspecified+no_connect"))
    )
    (net (code "67") (name "unconnected-(SW1-Pad2)") (class "Default")
      (node (ref "SW1") (pin "2") (pinfunction "2_2") (pintype "unspecified+no_connect"))
    )
    (net (code "68") (name "unconnected-(SW2-Pad1)") (class "Default")
      (node (ref "SW2") (pin "1") (pinfunction "1_1") (pintype "unspecified+no_connect"))
    )
    (net (code "69") (name "unconnected-(SW2-Pad2)") (class "Default")
      (node (ref "SW2") (pin "2") (pinfunction "2_2") (pintype "unspecified+no_connect"))
    )
    (net (code "70") (name "unconnected-(U1-NC-Pad4)") (class "Default")
      (node (ref "U1") (pin "4") (pinfunction "NC_4") (pintype "unspecified+no_connect"))
    )
    (net (code "71") (name "unconnected-(U2-NC-Pad4)") (class "Default")
      (node (ref "U2") (pin "4") (pinfunction "NC_4") (pintype "unspecified+no_connect"))
    )
    (net (code "72") (name "unconnected-(U3-NC-Pad17)") (class "Default")
      (node (ref "U3") (pin "17") (pinfunction "NC_17") (pintype "bidirectional+no_connect"))
    )
    (net (code "73") (name "unconnected-(U3-RES-Pad28)") (class "Default")
      (node (ref "U3") (pin "28") (pinfunction "RES_28") (pintype "bidirectional+no_connect"))
    )
    (net (code "74") (name "unconnected-(U3-RES-Pad29)") (class "Default")
      (node (ref "U3") (pin "29") (pinfunction "RES_29") (pintype "bidirectional+no_connect"))
    )
    (net (code "75") (name "unconnected-(U3-RES-Pad31)") (class "Default")
      (node (ref "U3") (pin "31") (pinfunction "RES_31") (pintype "bidirectional+no_connect"))
    )
    (net (code "76") (name "unconnected-(U3-RES-Pad32)") (class "Default")
      (node (ref "U3") (pin "32") (pinfunction "RES_32") (pintype "bidirectional+no_connect"))
    )
    (net (code "77") (name "unconnected-(U5-1-PadNC)") (class "Default")
      (node (ref "U5") (pin "NC") (pinfunction "1_NC") (pintype "unspecified+no_connect"))
    )
    (net (code "78") (name "unconnected-(U6-NC-Pad4)") (class "Default")
      (node (ref "U6") (pin "4") (pinfunction "NC_4") (pintype "unspecified+no_connect"))
    )
    (net (code "79") (name "unconnected-(U7-SW-Pad4)") (class "Default")
      (node (ref "U7") (pin "4") (pinfunction "SW_4") (pintype "unspecified+no_connect"))
    )
    (net (code "80") (name "unconnected-(U7-SW-Pad4)_1") (class "Default")
      (node (ref "U7") (pin "4") (pinfunction "SW_4") (pintype "unspecified+no_connect"))
    )
    (net (code "81") (name "unconnected-(U7-SW-Pad4)_2") (class "Default")
      (node (ref "U7") (pin "4") (pinfunction "SW_4") (pintype "unspecified+no_connect"))
    )
    (net (code "82") (name "unconnected-(X2-SBU1-PadA8)") (class "Default")
      (node (ref "X2") (pin "A8") (pinfunction "SBU1_A8") (pintype "bidirectional+no_connect"))
    )
    (net (code "83") (name "unconnected-(X2-SBU2-PadB8)") (class "Default")
      (node (ref "X2") (pin "B8") (pinfunction "SBU2_B8") (pintype "bidirectional+no_connect"))
    )
  )
)
